# RADM-USB-S03-V00.net
KiCad netlist of a schematic drawn in Altium Designer
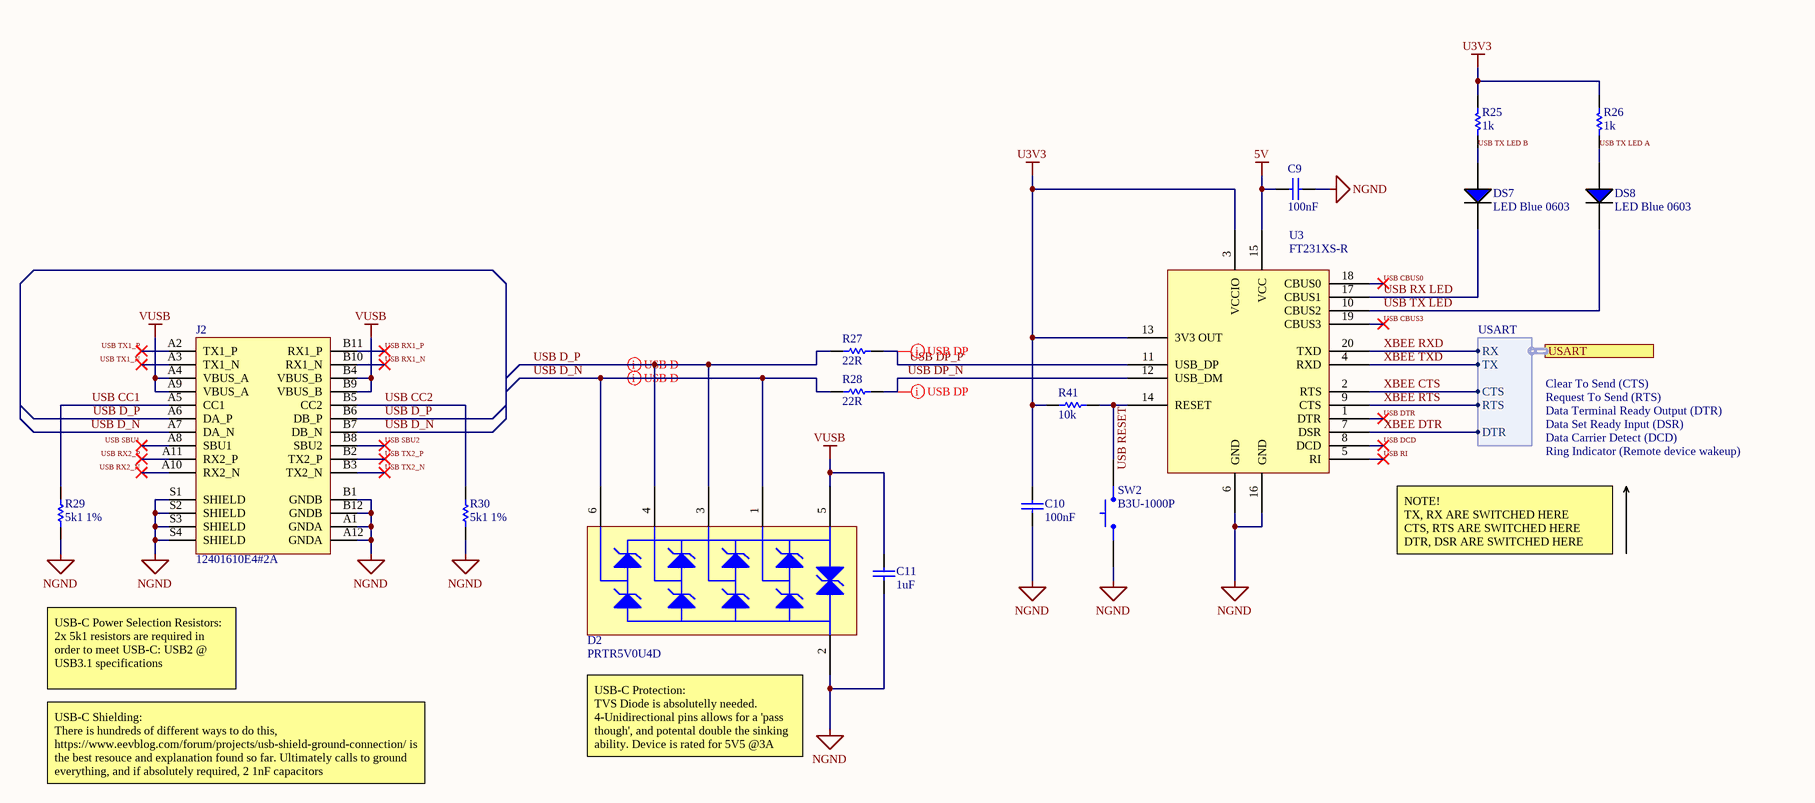
[diagram p0: RADM-USB-S03-V00.SchDoc]

(export (version "E")
  (design (tool "Eeschema 10.0.6"))
  (components
    (comp (ref "C9")
      (value "100nF")
      (footprint "Cap_Ceramic_0603")
      (description "Capacitor, Ceramic, SMD, 100nF, 50V, 5%, X7R, 0603")
      (libsource (lib "StandardCapacitors") (part "100nF 50V 5% X7R 0603"))
    )
    (comp (ref "C10")
      (value "100nF")
      (footprint "Cap_Ceramic_0603")
      (description "Capacitor, Ceramic, SMD, 100nF, 50V, 5%, X7R, 0603")
      (libsource (lib "StandardCapacitors") (part "100nF 50V 5% X7R 0603"))
    )
    (comp (ref "C11")
      (value "1uF")
      (footprint "Cap_Ceramic_0603")
      (description "Capacitor, Ceramic, SMD, 1uF, 25V, 5%, X7R, 0603")
      (libsource (lib "StandardCapacitors") (part "1uF 25V 5% X7R 0603"))
    )
    (comp (ref "D2")
      (value "PRTR5V0U4D")
      (footprint "SC-47")
      (description "Clamp Ipp Tvs Diode Surface Mount 6-TSOP")
      (libsource (lib "QUTMS_DiodeLibrary") (part "PRTR5V0U4D"))
    )
    (comp (ref "DS7")
      (value "LED Blue 0603")
      (footprint "LED BLUE 0603")
      (libsource (lib "QUTMS_LEDLibrary") (part "LED Blue 0603"))
    )
    (comp (ref "DS8")
      (value "LED Blue 0603")
      (footprint "LED BLUE 0603")
      (libsource (lib "QUTMS_LEDLibrary") (part "LED Blue 0603"))
    )
    (comp (ref "J2")
      (value "12401610E4#2A")
      (footprint "12401610E4#2A")
      (libsource (lib "QUTMS_USBLibrary") (part "12401610E4#2A"))
    )
    (comp (ref "R25")
      (value "1k")
      (footprint "Res_ThinFilm_0603")
      (description "Resistor, SMD, 1k, 0.1W, 5%, 0603")
      (libsource (lib "StandardResistors") (part "1k 5% 0603"))
    )
    (comp (ref "R26")
      (value "1k")
      (footprint "Res_ThinFilm_0603")
      (description "Resistor, SMD, 1k, 0.1W, 5%, 0603")
      (libsource (lib "StandardResistors") (part "1k 5% 0603"))
    )
    (comp (ref "R27")
      (value "22R")
      (footprint "Res_ThinFilm_0603")
      (description "Resistor, SMD, 22R, 0.1W, 5%, 0603")
      (libsource (lib "StandardResistors") (part "22R 5% 0603"))
    )
    (comp (ref "R28")
      (value "22R")
      (footprint "Res_ThinFilm_0603")
      (description "Resistor, SMD, 22R, 0.1W, 5%, 0603")
      (libsource (lib "StandardResistors") (part "22R 5% 0603"))
    )
    (comp (ref "R29")
      (value "5k1 1%")
      (footprint "Res_ThinFilm_0603")
      (description "Resistor, SMD, 5k1, 0.1W, 1%, 0603")
      (libsource (lib "StandardResistors") (part "5k1 1% 0603"))
    )
    (comp (ref "R30")
      (value "5k1 1%")
      (footprint "Res_ThinFilm_0603")
      (description "Resistor, SMD, 5k1, 0.1W, 1%, 0603")
      (libsource (lib "StandardResistors") (part "5k1 1% 0603"))
    )
    (comp (ref "R41")
      (value "10k")
      (footprint "Res_ThinFilm_0603")
      (description "Resistor, SMD, 10k, 0.1W, 5%, 0603")
      (libsource (lib "StandardResistors") (part "10k 5% 0603"))
    )
    (comp (ref "SW2")
      (value "B3U-1000P")
      (footprint "BTN B3U-1000P")
      (description "Omron B3U-1000P Ultra Miniture Switch")
      (libsource (lib "QUTMS_SwitchLibrary") (part "BTN B3U-1000P"))
    )
    (comp (ref "U3")
      (value "FT231XS-R")
      (footprint "SSOP-20")
      (description "USB Bridge, USB to UART USB 2.0 UART Interface 20-SSOP")
      (libsource (lib "QUTMS_USBLibrary") (part "FT231XS-R"))
    )
  )
  (nets
    (net (code "2") (name "/USB CBUS0") (class "Default")
      (node (ref "U3") (pin "18") (pinfunction "CBUS0_18") (pintype "passive+no_connect"))
    )
    (net (code "3") (name "/USB CBUS3") (class "Default")
      (node (ref "U3") (pin "19") (pinfunction "CBUS3_19") (pintype "passive+no_connect"))
    )
    (net (code "4") (name "/USB CC1") (class "Default")
      (node (ref "J2") (pin "A5") (pinfunction "CC1_A5") (pintype "passive"))
      (node (ref "R29") (pin "2") (pinfunction "2_2") (pintype "passive"))
    )
    (net (code "5") (name "/USB CC2") (class "Default")
      (node (ref "J2") (pin "B5") (pinfunction "CC2_B5") (pintype "passive"))
      (node (ref "R30") (pin "2") (pinfunction "2_2") (pintype "passive"))
    )
    (net (code "6") (name "/USB DCD") (class "Default")
      (node (ref "U3") (pin "8") (pinfunction "DCD_8") (pintype "passive+no_connect"))
    )
    (net (code "7") (name "/USB DP_N") (class "Default")
      (node (ref "R28") (pin "2") (pinfunction "2_2") (pintype "passive"))
      (node (ref "U3") (pin "12") (pinfunction "USB_DM_12") (pintype "passive"))
    )
    (net (code "8") (name "/USB DP_P") (class "Default")
      (node (ref "R27") (pin "2") (pinfunction "2_2") (pintype "passive"))
      (node (ref "U3") (pin "11") (pinfunction "USB_DP_11") (pintype "passive"))
    )
    (net (code "9") (name "/USB DTR") (class "Default")
      (node (ref "U3") (pin "1") (pinfunction "DTR_1") (pintype "passive+no_connect"))
    )
    (net (code "10") (name "/USB D_N") (class "Default")
      (node (ref "D2") (pin "1") (pinfunction "P1_1") (pintype "passive"))
      (node (ref "D2") (pin "6") (pinfunction "P4_6") (pintype "passive"))
      (node (ref "J2") (pin "A7") (pinfunction "DA_N_A7") (pintype "passive"))
      (node (ref "J2") (pin "B7") (pinfunction "DB_N_B7") (pintype "passive"))
      (node (ref "R28") (pin "1") (pinfunction "1_1") (pintype "passive"))
    )
    (net (code "11") (name "/USB D_P") (class "Default")
      (node (ref "D2") (pin "3") (pinfunction "P2_3") (pintype "passive"))
      (node (ref "D2") (pin "4") (pinfunction "P3_4") (pintype "passive"))
      (node (ref "J2") (pin "A6") (pinfunction "DA_P_A6") (pintype "passive"))
      (node (ref "J2") (pin "B6") (pinfunction "DB_P_B6") (pintype "passive"))
      (node (ref "R27") (pin "1") (pinfunction "1_1") (pintype "passive"))
    )
    (net (code "12") (name "/USB RESET") (class "Default")
      (node (ref "R41") (pin "2") (pinfunction "2_2") (pintype "passive"))
      (node (ref "SW2") (pin "2") (pinfunction "2_2") (pintype "passive"))
      (node (ref "U3") (pin "14") (pinfunction "RESET_14") (pintype "passive"))
    )
    (net (code "13") (name "/USB RI") (class "Default")
      (node (ref "U3") (pin "5") (pinfunction "RI_5") (pintype "passive+no_connect"))
    )
    (net (code "14") (name "/USB RX LED") (class "Default")
      (node (ref "DS7") (pin "2") (pinfunction "C_2") (pintype "passive"))
      (node (ref "U3") (pin "17") (pinfunction "CBUS1_17") (pintype "passive"))
    )
    (net (code "15") (name "/USB RX1_N") (class "Default")
      (node (ref "J2") (pin "B10") (pinfunction "RX1_N_B10") (pintype "passive+no_connect"))
    )
    (net (code "16") (name "/USB RX1_P") (class "Default")
      (node (ref "J2") (pin "B11") (pinfunction "RX1_P_B11") (pintype "passive+no_connect"))
    )
    (net (code "17") (name "/USB RX2_N") (class "Default")
      (node (ref "J2") (pin "A10") (pinfunction "RX2_N_A10") (pintype "passive+no_connect"))
    )
    (net (code "18") (name "/USB RX2_P") (class "Default")
      (node (ref "J2") (pin "A11") (pinfunction "RX2_P_A11") (pintype "passive+no_connect"))
    )
    (net (code "19") (name "/USB SBU1") (class "Default")
      (node (ref "J2") (pin "A8") (pinfunction "SBU1_A8") (pintype "passive+no_connect"))
    )
    (net (code "20") (name "/USB SBU2") (class "Default")
      (node (ref "J2") (pin "B8") (pinfunction "SBU2_B8") (pintype "passive+no_connect"))
    )
    (net (code "21") (name "/USB TX LED") (class "Default")
      (node (ref "DS8") (pin "2") (pinfunction "C_2") (pintype "passive"))
      (node (ref "U3") (pin "10") (pinfunction "CBUS2_10") (pintype "passive"))
    )
    (net (code "22") (name "/USB TX LED A") (class "Default")
      (node (ref "DS8") (pin "1") (pinfunction "A_1") (pintype "passive"))
      (node (ref "R26") (pin "2") (pinfunction "2_2") (pintype "passive"))
    )
    (net (code "23") (name "/USB TX LED B") (class "Default")
      (node (ref "DS7") (pin "1") (pinfunction "A_1") (pintype "passive"))
      (node (ref "R25") (pin "2") (pinfunction "2_2") (pintype "passive"))
    )
    (net (code "24") (name "/USB TX1_N") (class "Default")
      (node (ref "J2") (pin "A3") (pinfunction "TX1_N_A3") (pintype "passive+no_connect"))
    )
    (net (code "25") (name "/USB TX1_P") (class "Default")
      (node (ref "J2") (pin "A2") (pinfunction "TX1_P_A2") (pintype "passive+no_connect"))
    )
    (net (code "26") (name "/USB TX2_N") (class "Default")
      (node (ref "J2") (pin "B3") (pinfunction "TX2_N_B3") (pintype "passive+no_connect"))
    )
    (net (code "27") (name "/USB TX2_P") (class "Default")
      (node (ref "J2") (pin "B2") (pinfunction "TX2_P_B2") (pintype "passive+no_connect"))
    )
    (net (code "28") (name "/XBEE CTS") (class "Default")
      (node (ref "U3") (pin "2") (pinfunction "RTS_2") (pintype "passive"))
    )
    (net (code "29") (name "/XBEE DTR") (class "Default")
      (node (ref "U3") (pin "7") (pinfunction "DSR_7") (pintype "passive"))
    )
    (net (code "30") (name "/XBEE RTS") (class "Default")
      (node (ref "U3") (pin "9") (pinfunction "CTS_9") (pintype "passive"))
    )
    (net (code "31") (name "/XBEE RXD") (class "Default")
      (node (ref "U3") (pin "20") (pinfunction "TXD_20") (pintype "passive"))
    )
    (net (code "32") (name "/XBEE TXD") (class "Default")
      (node (ref "U3") (pin "4") (pinfunction "RXD_4") (pintype "passive"))
    )
    (net (code "34") (name "5V") (class "Default")
      (node (ref "C9") (pin "2") (pinfunction "2_2") (pintype "passive"))
      (node (ref "U3") (pin "15") (pinfunction "VCC_15") (pintype "passive"))
    )
    (net (code "35") (name "NGND") (class "Default")
      (node (ref "C10") (pin "1") (pinfunction "1_1") (pintype "passive"))
      (node (ref "C11") (pin "1") (pinfunction "1_1") (pintype "passive"))
      (node (ref "C9") (pin "1") (pinfunction "1_1") (pintype "passive"))
      (node (ref "D2") (pin "2") (pinfunction "GND_2") (pintype "passive"))
      (node (ref "J2") (pin "A1") (pinfunction "GNDA_A1") (pintype "passive"))
      (node (ref "J2") (pin "A12") (pinfunction "GNDA_A12") (pintype "passive"))
      (node (ref "J2") (pin "B1") (pinfunction "GNDB_B1") (pintype "passive"))
      (node (ref "J2") (pin "B12") (pinfunction "GNDB_B12") (pintype "passive"))
      (node (ref "J2") (pin "S1") (pinfunction "SHIELD_S1") (pintype "power_in"))
      (node (ref "J2") (pin "S2") (pinfunction "SHIELD_S2") (pintype "power_in"))
      (node (ref "J2") (pin "S3") (pinfunction "SHIELD_S3") (pintype "power_in"))
      (node (ref "J2") (pin "S4") (pinfunction "SHIELD_S4") (pintype "power_in"))
      (node (ref "R29") (pin "1") (pinfunction "1_1") (pintype "passive"))
      (node (ref "R30") (pin "1") (pinfunction "1_1") (pintype "passive"))
      (node (ref "SW2") (pin "1") (pinfunction "1_1") (pintype "passive"))
      (node (ref "U3") (pin "16") (pinfunction "GND_16") (pintype "passive"))
      (node (ref "U3") (pin "6") (pinfunction "GND_6") (pintype "passive"))
    )
    (net (code "36") (name "U3V3") (class "Default")
      (node (ref "C10") (pin "2") (pinfunction "2_2") (pintype "passive"))
      (node (ref "R25") (pin "1") (pinfunction "1_1") (pintype "passive"))
      (node (ref "R26") (pin "1") (pinfunction "1_1") (pintype "passive"))
      (node (ref "R41") (pin "1") (pinfunction "1_1") (pintype "passive"))
      (node (ref "U3") (pin "13") (pinfunction "3V3_OUT_13") (pintype "passive"))
      (node (ref "U3") (pin "3") (pinfunction "VCCIO_3") (pintype "passive"))
    )
    (net (code "37") (name "VUSB") (class "Default")
      (node (ref "C11") (pin "2") (pinfunction "2_2") (pintype "passive"))
      (node (ref "D2") (pin "5") (pinfunction "VCC_5") (pintype "passive"))
      (node (ref "J2") (pin "A4") (pinfunction "VBUS_A_A4") (pintype "passive"))
      (node (ref "J2") (pin "A9") (pinfunction "VBUS_A_A9") (pintype "passive"))
      (node (ref "J2") (pin "B4") (pinfunction "VBUS_B_B4") (pintype "passive"))
      (node (ref "J2") (pin "B9") (pinfunction "VBUS_B_B9") (pintype "passive"))
    )
  )
)
